# SCH_STM32_Blue_Pill_2022-05-05.net
KiCad netlist of a schematic drawn in EasyEDA
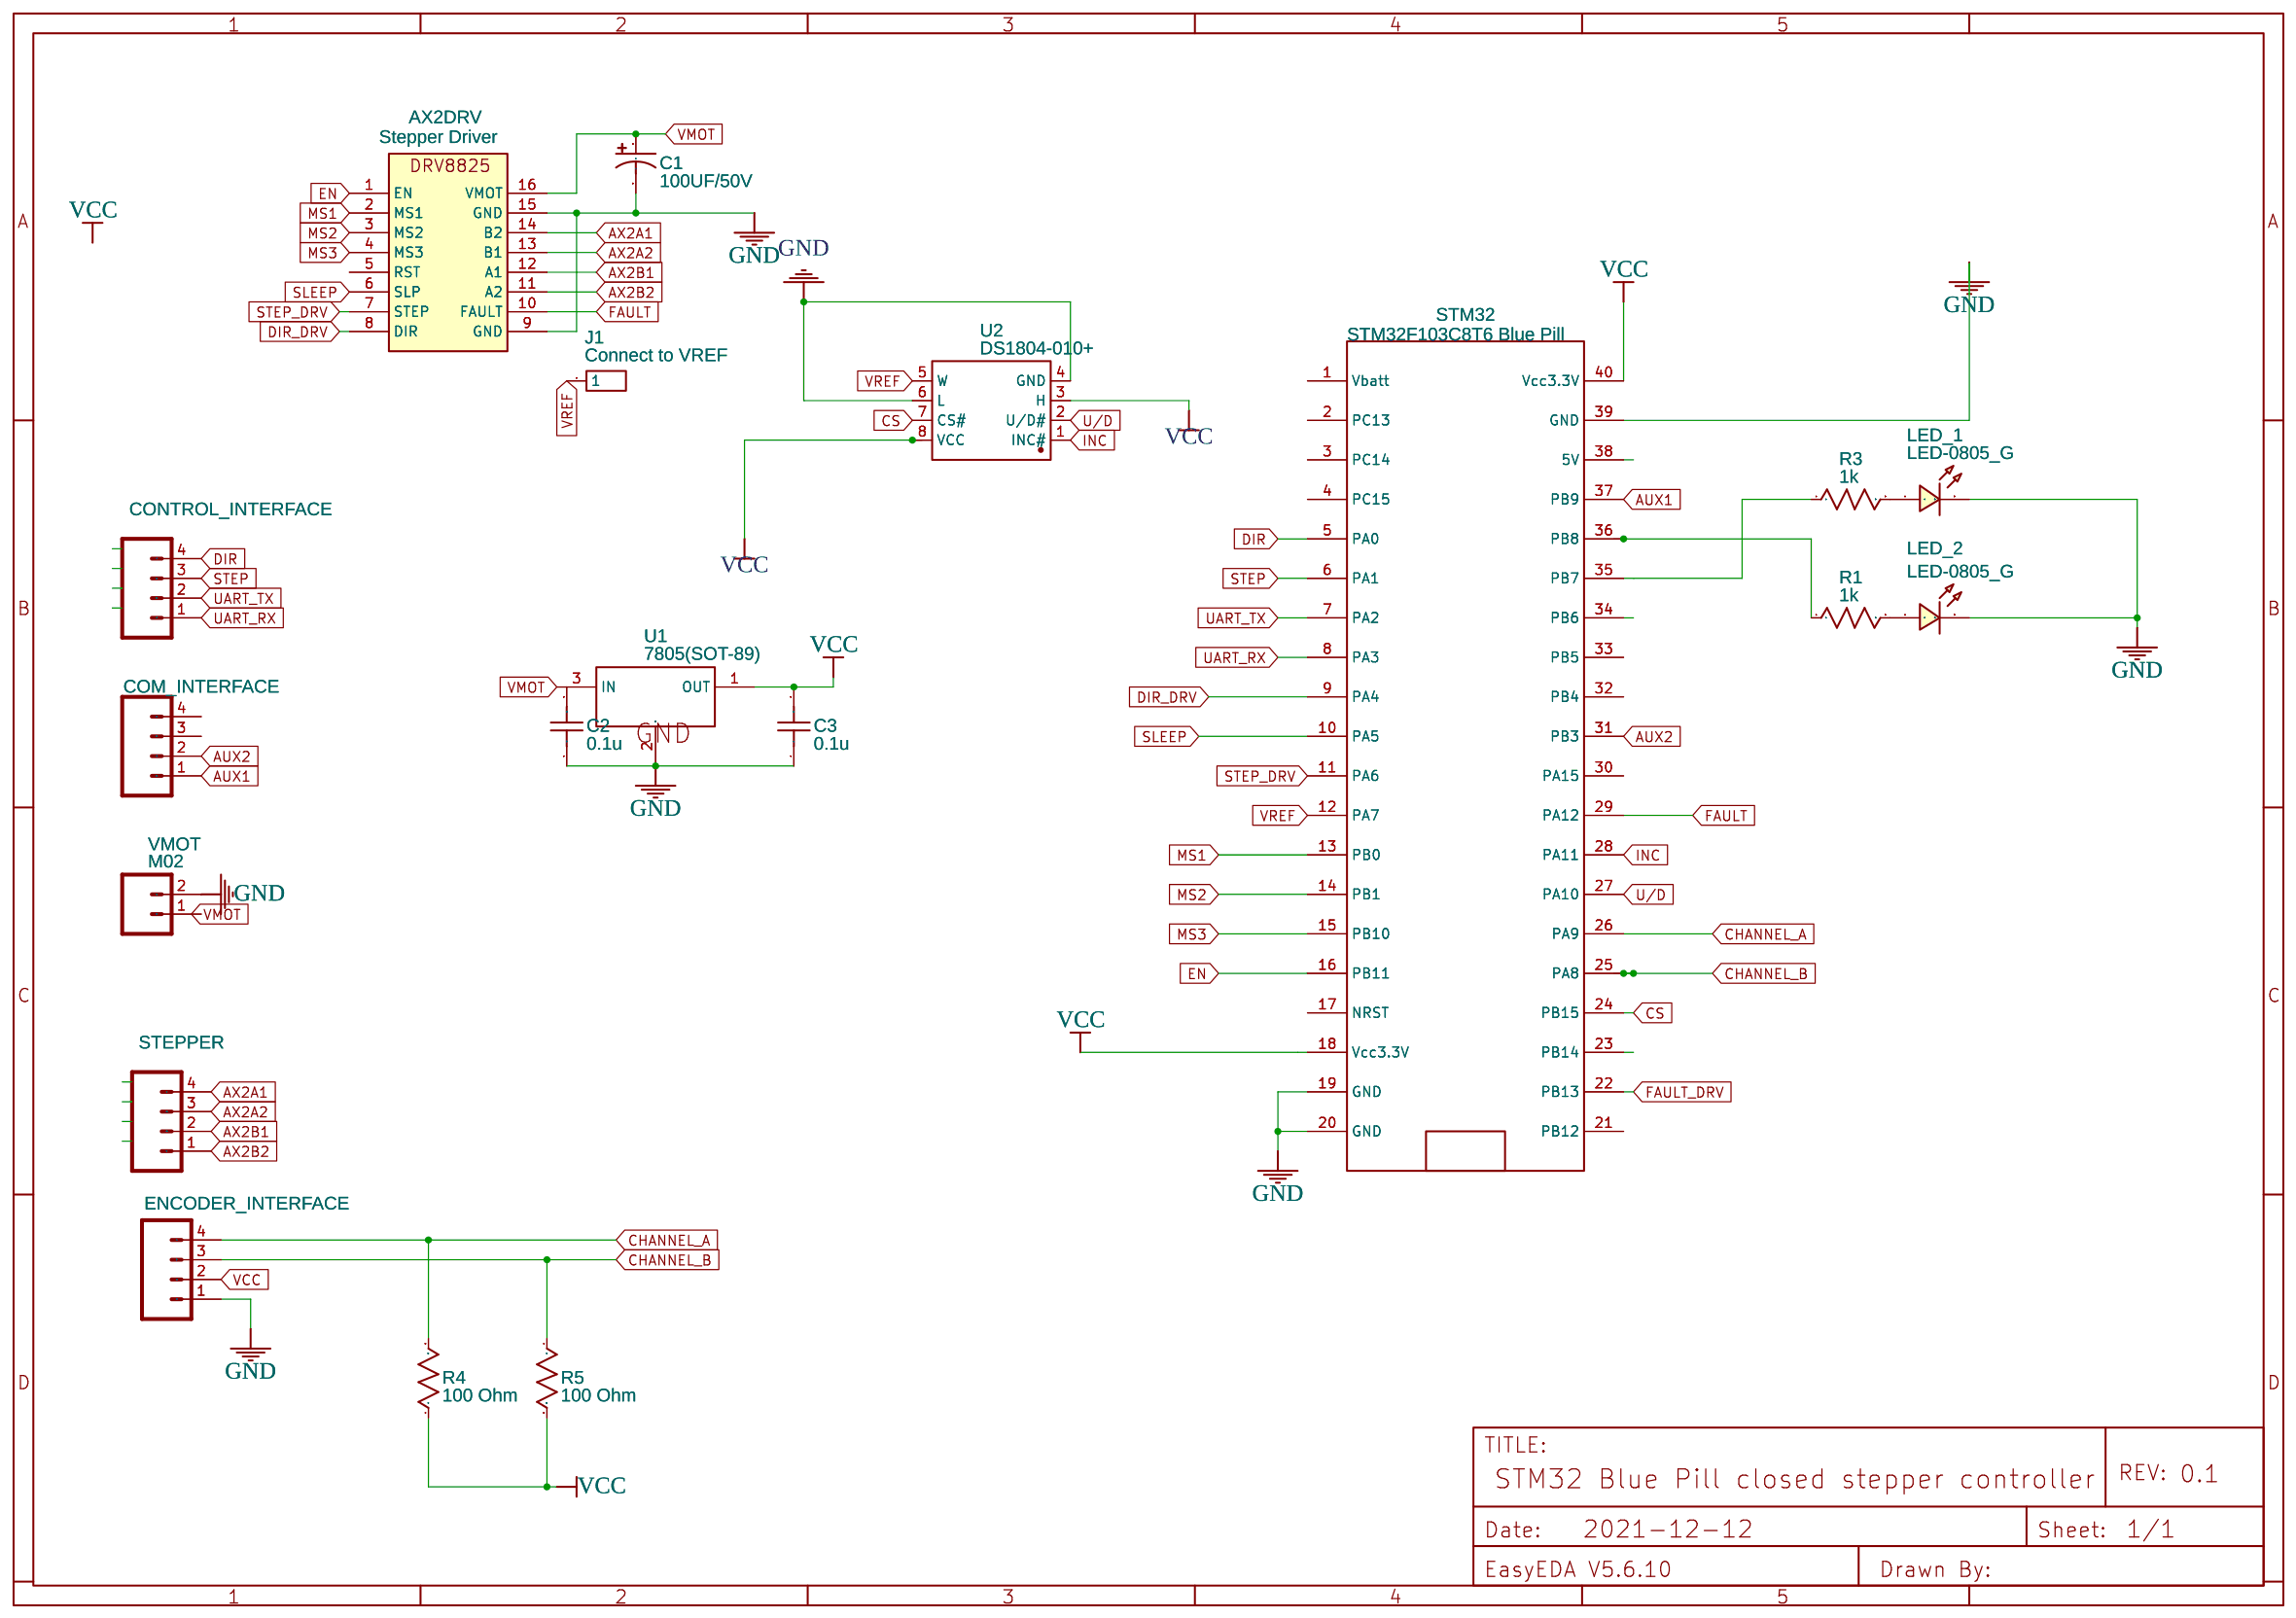
[diagram p0: schematic sheet]

(export (version "E")
  (design (tool "Eeschema 10.0.6"))
  (components
    (comp (ref "AX2DRV")
      (value "Stepper Driver")
      (libsource (lib "") (part "DRV8825 Stepper Motor Driver Carrier"))
    )
    (comp (ref "C1") (value "100UF/50V") (libsource (lib "") (part "100UF/50V")))
    (comp (ref "C2") (value "0.1u") (libsource (lib "") (part "C_0603_US")))
    (comp (ref "C3") (value "0.1u") (libsource (lib "") (part "C_0603_US")))
    (comp (ref "COM_IF") (value "COM_INTERFACE") (libsource (lib "") (part "M04_3")))
    (comp (ref "CTR_IF") (value "CONTROL_INTERFACE") (libsource (lib "") (part "M04_2")))
    (comp (ref "ENC_IF") (value "ENCODER_INTERFACE") (libsource (lib "") (part "M04_1")))
    (comp (ref "J1")
      (value "Connect to VREF")
      (fields (field (name "BOM_Supplier Part") "C81276"))
      (libsource (lib "") (part "HDR-M-2.54_1x1"))
    )
    (comp (ref "LED_1")
      (value "LED-0805_G")
      (fields (field (name "BOM_Manufacturer Part") "NCD0805G1") (field (name "BOM_Supplier Part") "C84260"))
      (libsource (lib "") (part "LED-0805_G"))
    )
    (comp (ref "LED_2")
      (value "LED-0805_G")
      (fields (field (name "BOM_Manufacturer Part") "NCD0805G1") (field (name "BOM_Supplier Part") "C84260"))
      (libsource (lib "") (part "LED-0805_G"))
    )
    (comp (ref "R1") (value "1k") (libsource (lib "") (part "R_0603_US")))
    (comp (ref "R3") (value "1k") (libsource (lib "") (part "R_0603_US")))
    (comp (ref "R4") (value "100 Ohm") (libsource (lib "") (part "R_0603_US_1")))
    (comp (ref "R5") (value "100 Ohm") (libsource (lib "") (part "R_0603_US_2")))
    (comp (ref "STM32")
      (value "STM32F103C8T6 Blue Pill")
      (fields (field (name "BOM_Manufacturer Part") "STM32Duino"))
      (libsource (lib "") (part "STM32F103C8T6 Generic Development Board"))
    )
    (comp (ref "STP") (value "STEPPER") (libsource (lib "") (part "M04")))
    (comp (ref "U1")
      (value "7805(SOT-89)")
      (fields (field (name "BOM_Manufacturer Part") "CJ78L05") (field (name "BOM_Supplier Part") "C2079"))
      (libsource (lib "") (part "7805(SOT-89)"))
    )
    (comp (ref "U2")
      (value "DS1804-010+")
      (fields (field (name "BOM_Supplier Part") "C1520917"))
      (libsource (lib "") (part "DS1804-010+"))
    )
    (comp (ref "VMOT") (value "M02") (libsource (lib "") (part "M02")))
  )
  (nets
    (net (code "1") (name "AUX1") (class "Default")
      (node (ref "COM_IF") (pin "1") (pinfunction "1_1") (pintype "unspecified"))
      (node (ref "STM32") (pin "37") (pinfunction "PB9_37") (pintype "unspecified"))
    )
    (net (code "2") (name "AUX2") (class "Default")
      (node (ref "COM_IF") (pin "2") (pinfunction "2_2") (pintype "unspecified"))
      (node (ref "STM32") (pin "31") (pinfunction "PB3_31") (pintype "unspecified"))
    )
    (net (code "3") (name "AX2A1") (class "Default")
      (node (ref "AX2DRV") (pin "14") (pinfunction "B2_14") (pintype "unspecified"))
      (node (ref "STP") (pin "4") (pinfunction "4_4") (pintype "unspecified"))
    )
    (net (code "4") (name "AX2A2") (class "Default")
      (node (ref "AX2DRV") (pin "13") (pinfunction "B1_13") (pintype "unspecified"))
      (node (ref "STP") (pin "3") (pinfunction "3_3") (pintype "unspecified"))
    )
    (net (code "5") (name "AX2B1") (class "Default")
      (node (ref "AX2DRV") (pin "12") (pinfunction "A1_12") (pintype "unspecified"))
      (node (ref "STP") (pin "2") (pinfunction "2_2") (pintype "unspecified"))
    )
    (net (code "6") (name "AX2B2") (class "Default")
      (node (ref "AX2DRV") (pin "11") (pinfunction "A2_11") (pintype "unspecified"))
      (node (ref "STP") (pin "1") (pinfunction "1_1") (pintype "unspecified"))
    )
    (net (code "7") (name "CHANNEL_A") (class "Default")
      (node (ref "ENC_IF") (pin "4") (pinfunction "4_4") (pintype "unspecified"))
      (node (ref "R4") (pin "2") (pinfunction "2_2") (pintype "unspecified"))
      (node (ref "STM32") (pin "26") (pinfunction "PA9_26") (pintype "unspecified"))
    )
    (net (code "8") (name "CHANNEL_B") (class "Default")
      (node (ref "ENC_IF") (pin "3") (pinfunction "3_3") (pintype "unspecified"))
      (node (ref "R5") (pin "1") (pinfunction "1_1") (pintype "unspecified"))
      (node (ref "STM32") (pin "25") (pinfunction "PA8_25") (pintype "unspecified"))
    )
    (net (code "9") (name "CS") (class "Default")
      (node (ref "STM32") (pin "24") (pinfunction "PB15_24") (pintype "unspecified"))
      (node (ref "U2") (pin "7") (pinfunction "CS#_7") (pintype "unspecified"))
    )
    (net (code "10") (name "DIR") (class "Default")
      (node (ref "CTR_IF") (pin "4") (pinfunction "4_4") (pintype "unspecified"))
      (node (ref "STM32") (pin "5") (pinfunction "PA0_5") (pintype "unspecified"))
    )
    (net (code "11") (name "DIR_DRV") (class "Default")
      (node (ref "AX2DRV") (pin "8") (pinfunction "DIR_8") (pintype "unspecified"))
      (node (ref "STM32") (pin "9") (pinfunction "PA4_9") (pintype "unspecified"))
    )
    (net (code "12") (name "EN") (class "Default")
      (node (ref "AX2DRV") (pin "1") (pinfunction "EN_1") (pintype "unspecified"))
      (node (ref "STM32") (pin "16") (pinfunction "PB11_16") (pintype "unspecified"))
    )
    (net (code "13") (name "FAULT") (class "Default")
      (node (ref "AX2DRV") (pin "10") (pinfunction "FAULT_10") (pintype "unspecified"))
      (node (ref "STM32") (pin "29") (pinfunction "PA12_29") (pintype "unspecified"))
    )
    (net (code "14") (name "FAULT_DRV") (class "Default")
      (node (ref "STM32") (pin "22") (pinfunction "PB13_22") (pintype "unspecified"))
    )
    (net (code "15") (name "GND") (class "Default")
      (node (ref "AX2DRV") (pin "15") (pinfunction "GND_15") (pintype "unspecified"))
      (node (ref "AX2DRV") (pin "9") (pinfunction "GND_9") (pintype "unspecified"))
      (node (ref "C1") (pin "2") (pinfunction "-_2") (pintype "unspecified"))
      (node (ref "C2") (pin "1") (pinfunction "1_1") (pintype "unspecified"))
      (node (ref "C3") (pin "1") (pinfunction "1_1") (pintype "unspecified"))
      (node (ref "ENC_IF") (pin "1") (pinfunction "1_1") (pintype "unspecified"))
      (node (ref "LED_1") (pin "2") (pinfunction "2_2") (pintype "unspecified"))
      (node (ref "LED_2") (pin "2") (pinfunction "2_2") (pintype "unspecified"))
      (node (ref "STM32") (pin "19") (pinfunction "GND_19") (pintype "unspecified"))
      (node (ref "STM32") (pin "20") (pinfunction "GND_20") (pintype "unspecified"))
      (node (ref "STM32") (pin "39") (pinfunction "GND_39") (pintype "unspecified"))
      (node (ref "U1") (pin "2") (pinfunction "GND_2") (pintype "passive"))
      (node (ref "U2") (pin "4") (pinfunction "GND_4") (pintype "unspecified"))
      (node (ref "U2") (pin "6") (pinfunction "L_6") (pintype "unspecified"))
      (node (ref "VMOT") (pin "2") (pinfunction "2_2") (pintype "unspecified"))
    )
    (net (code "16") (name "INC") (class "Default")
      (node (ref "STM32") (pin "28") (pinfunction "PA11_28") (pintype "unspecified"))
      (node (ref "U2") (pin "1") (pinfunction "INC#_1") (pintype "unspecified"))
    )
    (net (code "17") (name "MS1") (class "Default")
      (node (ref "AX2DRV") (pin "2") (pinfunction "MS1_2") (pintype "unspecified"))
      (node (ref "STM32") (pin "13") (pinfunction "PB0_13") (pintype "unspecified"))
    )
    (net (code "18") (name "MS2") (class "Default")
      (node (ref "AX2DRV") (pin "3") (pinfunction "MS2_3") (pintype "unspecified"))
      (node (ref "STM32") (pin "14") (pinfunction "PB1_14") (pintype "unspecified"))
    )
    (net (code "19") (name "MS3") (class "Default")
      (node (ref "AX2DRV") (pin "4") (pinfunction "MS3_4") (pintype "unspecified"))
      (node (ref "STM32") (pin "15") (pinfunction "PB10_15") (pintype "unspecified"))
    )
    (net (code "20") (name "Net-(LED_1-Pad1)") (class "Default")
      (node (ref "LED_1") (pin "1") (pinfunction "1_1") (pintype "unspecified"))
      (node (ref "R3") (pin "2") (pinfunction "2_2") (pintype "unspecified"))
    )
    (net (code "21") (name "Net-(LED_2-Pad1)") (class "Default")
      (node (ref "LED_2") (pin "1") (pinfunction "1_1") (pintype "unspecified"))
      (node (ref "R1") (pin "2") (pinfunction "2_2") (pintype "unspecified"))
    )
    (net (code "22") (name "Net-(STM32-PB7)") (class "Default")
      (node (ref "R3") (pin "1") (pinfunction "1_1") (pintype "unspecified"))
      (node (ref "STM32") (pin "35") (pinfunction "PB7_35") (pintype "unspecified"))
    )
    (net (code "23") (name "Net-(STM32-PB8)") (class "Default")
      (node (ref "R1") (pin "1") (pinfunction "1_1") (pintype "unspecified"))
      (node (ref "STM32") (pin "36") (pinfunction "PB8_36") (pintype "unspecified"))
    )
    (net (code "24") (name "SLEEP") (class "Default")
      (node (ref "AX2DRV") (pin "6") (pinfunction "SLP_6") (pintype "unspecified"))
      (node (ref "STM32") (pin "10") (pinfunction "PA5_10") (pintype "unspecified"))
    )
    (net (code "25") (name "STEP") (class "Default")
      (node (ref "CTR_IF") (pin "3") (pinfunction "3_3") (pintype "unspecified"))
      (node (ref "STM32") (pin "6") (pinfunction "PA1_6") (pintype "unspecified"))
    )
    (net (code "26") (name "STEP_DRV") (class "Default")
      (node (ref "AX2DRV") (pin "7") (pinfunction "STEP_7") (pintype "unspecified"))
      (node (ref "STM32") (pin "11") (pinfunction "PA6_11") (pintype "unspecified"))
    )
    (net (code "27") (name "UART_RX") (class "Default")
      (node (ref "CTR_IF") (pin "1") (pinfunction "1_1") (pintype "unspecified"))
      (node (ref "STM32") (pin "8") (pinfunction "PA3_8") (pintype "unspecified"))
    )
    (net (code "28") (name "UART_TX") (class "Default")
      (node (ref "CTR_IF") (pin "2") (pinfunction "2_2") (pintype "unspecified"))
      (node (ref "STM32") (pin "7") (pinfunction "PA2_7") (pintype "unspecified"))
    )
    (net (code "29") (name "U{slash}D") (class "Default")
      (node (ref "STM32") (pin "27") (pinfunction "PA10_27") (pintype "unspecified"))
      (node (ref "U2") (pin "2") (pinfunction "U/D#_2") (pintype "unspecified"))
    )
    (net (code "30") (name "VCC") (class "Default")
      (node (ref "C3") (pin "2") (pinfunction "2_2") (pintype "unspecified"))
      (node (ref "ENC_IF") (pin "2") (pinfunction "2_2") (pintype "unspecified"))
      (node (ref "R4") (pin "1") (pinfunction "1_1") (pintype "unspecified"))
      (node (ref "R5") (pin "2") (pinfunction "2_2") (pintype "unspecified"))
      (node (ref "STM32") (pin "18") (pinfunction "Vcc3.3V_18") (pintype "unspecified"))
      (node (ref "STM32") (pin "40") (pinfunction "Vcc3.3V_40") (pintype "unspecified"))
      (node (ref "U1") (pin "1") (pinfunction "OUT_1") (pintype "passive"))
      (node (ref "U2") (pin "3") (pinfunction "H_3") (pintype "unspecified"))
      (node (ref "U2") (pin "8") (pinfunction "VCC_8") (pintype "unspecified"))
    )
    (net (code "31") (name "VMOT") (class "Default")
      (node (ref "AX2DRV") (pin "16") (pinfunction "VMOT_16") (pintype "unspecified"))
      (node (ref "C1") (pin "1") (pinfunction "+_1") (pintype "unspecified"))
      (node (ref "U1") (pin "3") (pinfunction "IN_3") (pintype "passive"))
    )
    (net (code "32") (name "VREF") (class "Default")
      (node (ref "J1") (pin "1") (pinfunction "1_1") (pintype "input"))
      (node (ref "STM32") (pin "12") (pinfunction "PA7_12") (pintype "unspecified"))
      (node (ref "U2") (pin "5") (pinfunction "W_5") (pintype "unspecified"))
    )
    (net (code "33") (name "unconnected-(AX2DRV-RST-Pad5)") (class "Default")
      (node (ref "AX2DRV") (pin "5") (pinfunction "RST_5") (pintype "unspecified"))
    )
    (net (code "34") (name "unconnected-(C2-Pad2)") (class "Default")
      (node (ref "C2") (pin "2") (pinfunction "2_2") (pintype "unspecified"))
    )
    (net (code "35") (name "unconnected-(COM_IF-Pad3)") (class "Default")
      (node (ref "COM_IF") (pin "3") (pinfunction "3_3") (pintype "unspecified"))
    )
    (net (code "36") (name "unconnected-(COM_IF-Pad4)") (class "Default")
      (node (ref "COM_IF") (pin "4") (pinfunction "4_4") (pintype "unspecified"))
    )
    (net (code "37") (name "unconnected-(STM32-5V-Pad38)") (class "Default")
      (node (ref "STM32") (pin "38") (pinfunction "5V_38") (pintype "unspecified"))
    )
    (net (code "38") (name "unconnected-(STM32-NRST-Pad17)") (class "Default")
      (node (ref "STM32") (pin "17") (pinfunction "NRST_17") (pintype "unspecified"))
    )
    (net (code "39") (name "unconnected-(STM32-PA15-Pad30)") (class "Default")
      (node (ref "STM32") (pin "30") (pinfunction "PA15_30") (pintype "unspecified"))
    )
    (net (code "40") (name "unconnected-(STM32-PB4-Pad32)") (class "Default")
      (node (ref "STM32") (pin "32") (pinfunction "PB4_32") (pintype "unspecified"))
    )
    (net (code "41") (name "unconnected-(STM32-PB5-Pad33)") (class "Default")
      (node (ref "STM32") (pin "33") (pinfunction "PB5_33") (pintype "unspecified"))
    )
    (net (code "42") (name "unconnected-(STM32-PB6-Pad34)") (class "Default")
      (node (ref "STM32") (pin "34") (pinfunction "PB6_34") (pintype "unspecified"))
    )
    (net (code "43") (name "unconnected-(STM32-PB12-Pad21)") (class "Default")
      (node (ref "STM32") (pin "21") (pinfunction "PB12_21") (pintype "unspecified"))
    )
    (net (code "44") (name "unconnected-(STM32-PB14-Pad23)") (class "Default")
      (node (ref "STM32") (pin "23") (pinfunction "PB14_23") (pintype "unspecified"))
    )
    (net (code "45") (name "unconnected-(STM32-PC13-Pad2)") (class "Default")
      (node (ref "STM32") (pin "2") (pinfunction "PC13_2") (pintype "unspecified"))
    )
    (net (code "46") (name "unconnected-(STM32-PC14-Pad3)") (class "Default")
      (node (ref "STM32") (pin "3") (pinfunction "PC14_3") (pintype "unspecified"))
    )
    (net (code "47") (name "unconnected-(STM32-PC15-Pad4)") (class "Default")
      (node (ref "STM32") (pin "4") (pinfunction "PC15_4") (pintype "unspecified"))
    )
    (net (code "48") (name "unconnected-(STM32-Vbatt-Pad1)") (class "Default")
      (node (ref "STM32") (pin "1") (pinfunction "Vbatt_1") (pintype "unspecified"))
    )
    (net (code "49") (name "unconnected-(VMOT-Pad1)") (class "Default")
      (node (ref "VMOT") (pin "1") (pinfunction "1_1") (pintype "unspecified"))
    )
  )
)
